# LB_BIT_w2_BRANCH-v02_rev1.net
KiCad netlist of a schematic drawn in EAGLE
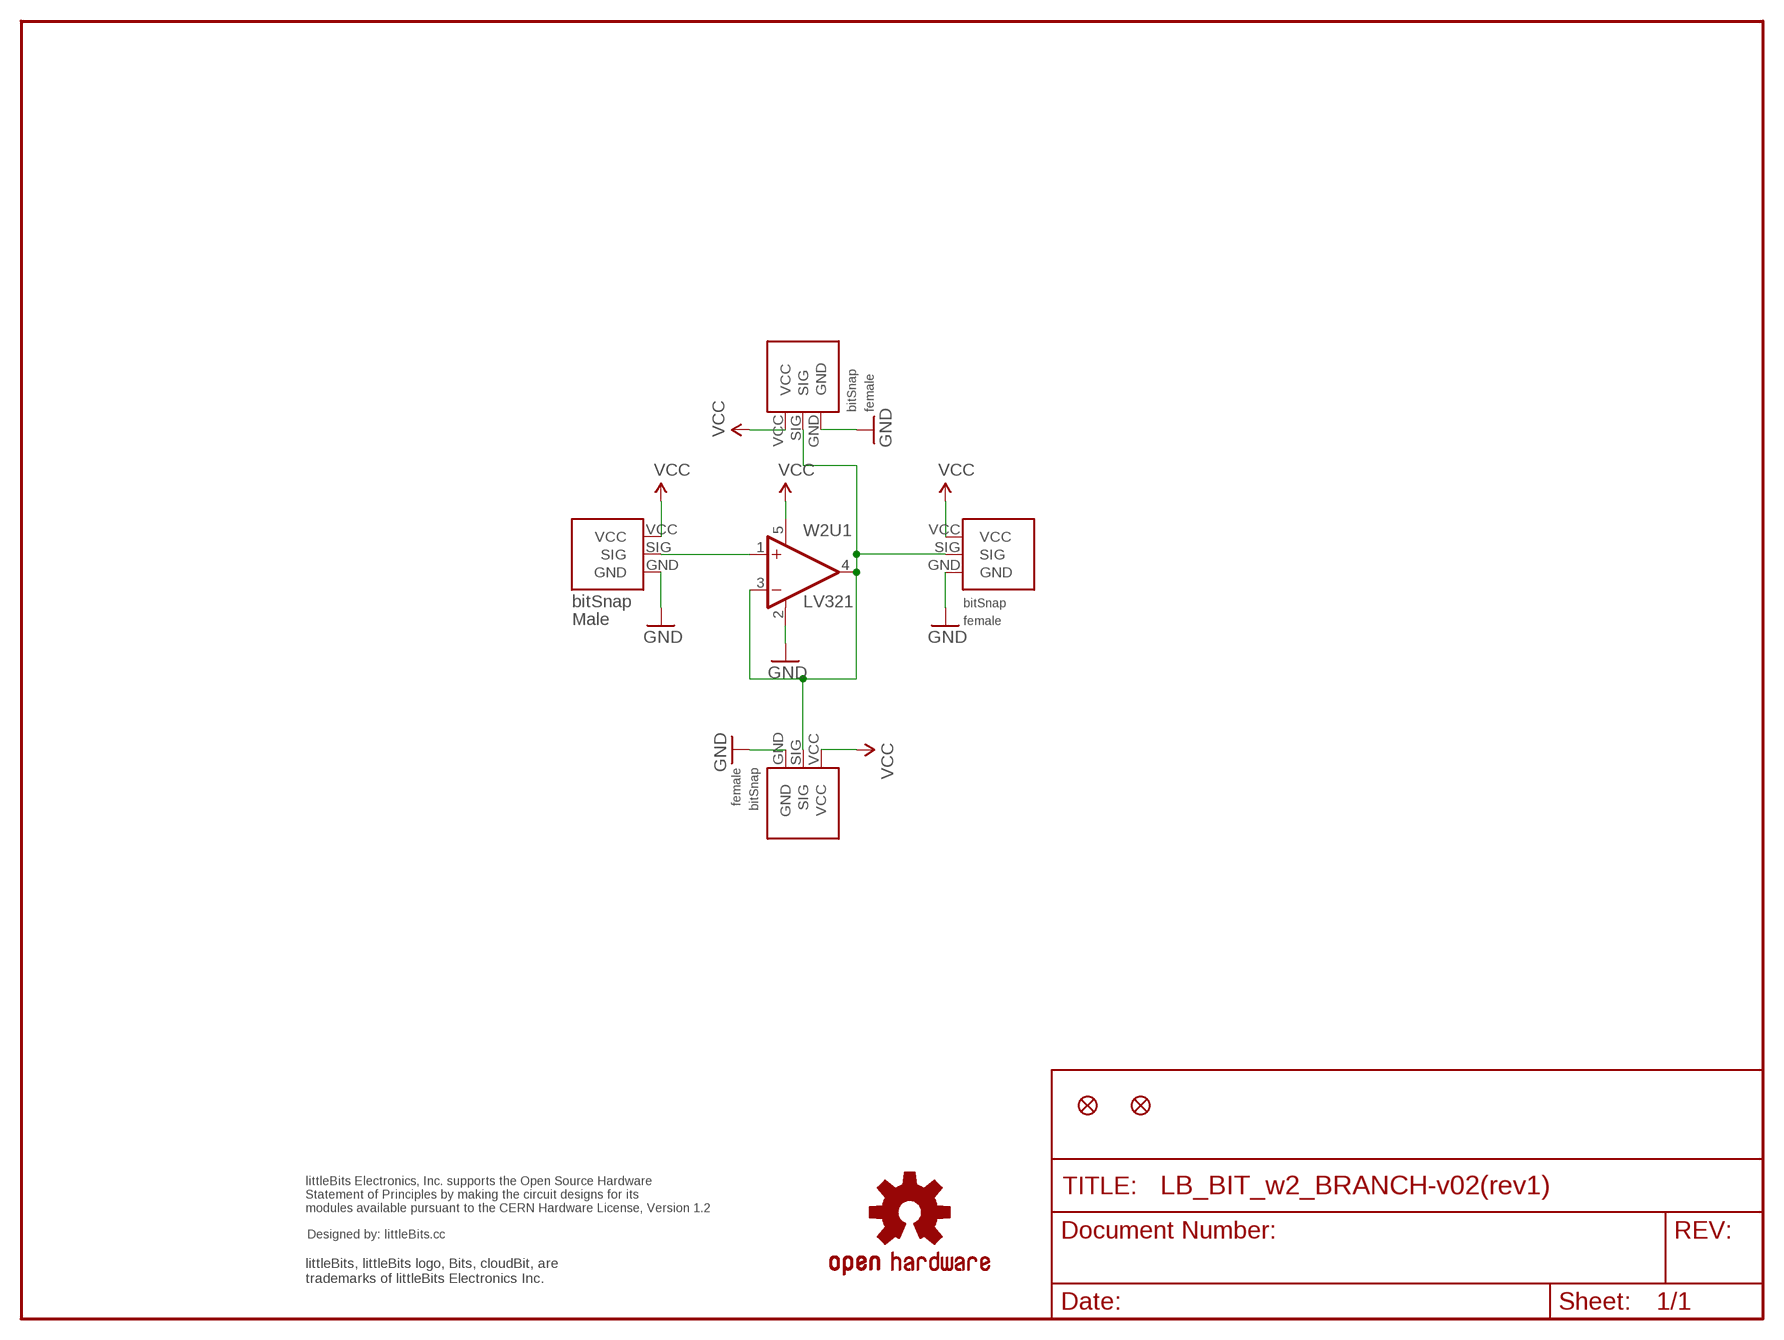
[diagram p0: schematic, sheet 1]

(export (version "E")
  (design (tool "Eeschema 10.0.6"))
  (components
    (comp (ref "JP1")
      (value "FIDUCIAL1X2")
      (footprint "eagle-import:FIDUCIAL-1X2")
      (libsource (lib "eagle-import") (part "FIDUCIAL1X2"))
    )
    (comp (ref "JP2")
      (value "FIDUCIAL1X2")
      (footprint "eagle-import:FIDUCIAL-1X2")
      (libsource (lib "eagle-import") (part "FIDUCIAL1X2"))
    )
    (comp (ref "U$1")
      (value "OSHWCREDIT")
      (footprint "eagle-import:OSHWCREDIT")
      (libsource (lib "eagle-import") (part "OSHWCREDIT"))
    )
    (comp (ref "U$6")
      (value "OSHW-LOGOL")
      (footprint "eagle-import:OSHW-LOGO-L")
      (libsource (lib "eagle-import") (part "OSHW-LOGOL"))
    )
    (comp (ref "W2BSF1")
      (value "BITSNAP_FEMALE")
      (footprint "eagle-import:BITSNAP_FEMALE")
      (libsource (lib "eagle-import") (part "BITSNAP_FEMALE"))
    )
    (comp (ref "W2BSF2")
      (value "BITSNAP_FEMALE")
      (footprint "eagle-import:BITSNAP_FEMALE")
      (libsource (lib "eagle-import") (part "BITSNAP_FEMALE"))
    )
    (comp (ref "W2BSF3")
      (value "BITSNAP_FEMALE")
      (footprint "eagle-import:BITSNAP_FEMALE")
      (libsource (lib "eagle-import") (part "BITSNAP_FEMALE"))
    )
    (comp (ref "W2BSM1")
      (value "BITSNAP_MALE")
      (footprint "eagle-import:BITSNAP_MALE")
      (libsource (lib "eagle-import") (part "BITSNAP_MALE"))
    )
    (comp (ref "W2U1")
      (value "LV321")
      (footprint "eagle-import:SC70-5")
      (libsource (lib "eagle-import") (part "LV321"))
    )
  )
  (nets
    (net (code "1") (name "GND") (class "Default")
      (node (ref "W2BSF1") (pin "GND") (pinfunction "GND_GND") (pintype "bidirectional"))
      (node (ref "W2BSF2") (pin "GND") (pinfunction "GND_GND") (pintype "bidirectional"))
      (node (ref "W2BSF3") (pin "GND") (pinfunction "GND_GND") (pintype "bidirectional"))
      (node (ref "W2BSM1") (pin "GND") (pinfunction "GND_GND") (pintype "bidirectional"))
      (node (ref "W2U1") (pin "2") (pinfunction "V-_2") (pintype "power_in"))
    )
    (net (code "2") (name "Net-(W2U1-+IN)") (class "Default")
      (node (ref "W2BSM1") (pin "SIG") (pinfunction "SIG_SIG") (pintype "bidirectional"))
      (node (ref "W2U1") (pin "1") (pinfunction "+IN_1") (pintype "input"))
    )
    (net (code "3") (name "Net-(W2U1--IN)") (class "Default")
      (node (ref "W2BSF1") (pin "SIG") (pinfunction "SIG_SIG") (pintype "bidirectional"))
      (node (ref "W2BSF2") (pin "SIG") (pinfunction "SIG_SIG") (pintype "bidirectional"))
      (node (ref "W2BSF3") (pin "SIG") (pinfunction "SIG_SIG") (pintype "bidirectional"))
      (node (ref "W2U1") (pin "3") (pinfunction "-IN_3") (pintype "input"))
      (node (ref "W2U1") (pin "4") (pinfunction "OUT_4") (pintype "output"))
    )
    (net (code "4") (name "VCC") (class "Default")
      (node (ref "W2BSF1") (pin "VCC") (pinfunction "VCC_VCC") (pintype "bidirectional"))
      (node (ref "W2BSF2") (pin "VCC") (pinfunction "VCC_VCC") (pintype "bidirectional"))
      (node (ref "W2BSF3") (pin "VCC") (pinfunction "VCC_VCC") (pintype "bidirectional"))
      (node (ref "W2BSM1") (pin "VCC") (pinfunction "VCC_VCC") (pintype "bidirectional"))
      (node (ref "W2U1") (pin "5") (pinfunction "V+_5") (pintype "power_in"))
    )
  )
)
